# BMS_DAISYCHAIN.net
KiCad netlist of a schematic drawn in Altium Designer
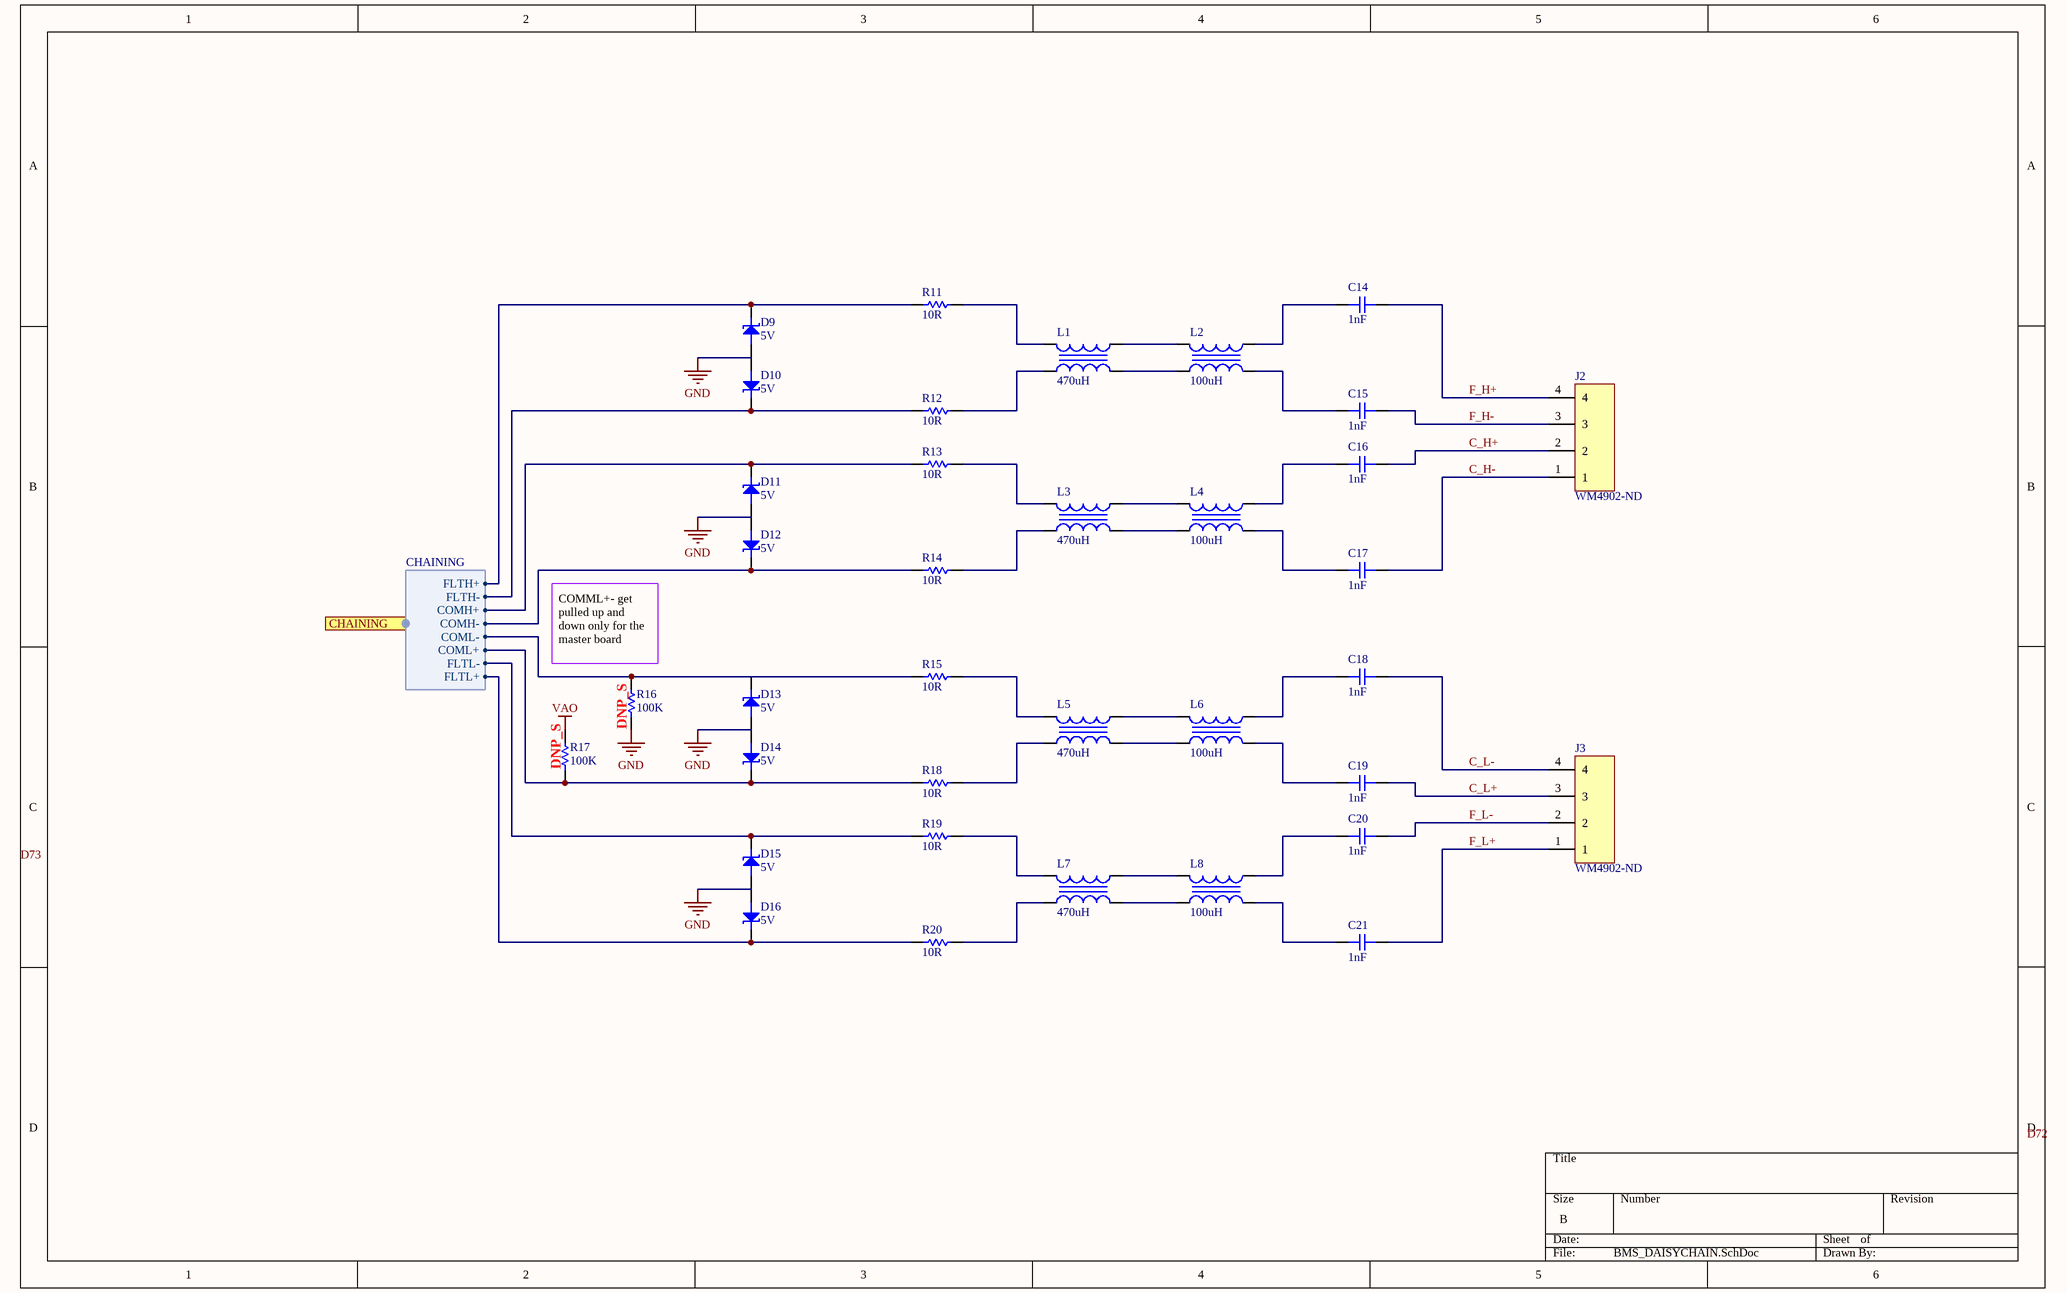
[diagram p0: BMS_DAISYCHAIN.SchDoc]

(export (version "E")
  (design (tool "Eeschema 10.0.6"))
  (components
    (comp (ref "C14")
      (value "1nF")
      (footprint "CAP-0603")
      (description "CAP CER 1000PF 50V X7R 0603")
      (fields
        (field (name "MANUFACTURER") "KEMET")
        (field (name "MANUFACTURER PART NUMBER") "C0603C102J5RACTU")
      )
      (libsource (lib "Capacitors") (part "0603-1nF-50V"))
    )
    (comp (ref "C15")
      (value "1nF")
      (footprint "CAP-0603")
      (description "CAP CER 1000PF 50V X7R 0603")
      (fields
        (field (name "MANUFACTURER") "KEMET")
        (field (name "MANUFACTURER PART NUMBER") "C0603C102J5RACTU")
      )
      (libsource (lib "Capacitors") (part "0603-1nF-50V"))
    )
    (comp (ref "C16")
      (value "1nF")
      (footprint "CAP-0603")
      (description "CAP CER 1000PF 50V X7R 0603")
      (fields
        (field (name "MANUFACTURER") "KEMET")
        (field (name "MANUFACTURER PART NUMBER") "C0603C102J5RACTU")
      )
      (libsource (lib "Capacitors") (part "0603-1nF-50V"))
    )
    (comp (ref "C17")
      (value "1nF")
      (footprint "CAP-0603")
      (description "CAP CER 1000PF 50V X7R 0603")
      (fields
        (field (name "MANUFACTURER") "KEMET")
        (field (name "MANUFACTURER PART NUMBER") "C0603C102J5RACTU")
      )
      (libsource (lib "Capacitors") (part "0603-1nF-50V"))
    )
    (comp (ref "C18")
      (value "1nF")
      (footprint "CAP-0603")
      (description "CAP CER 1000PF 50V X7R 0603")
      (fields
        (field (name "MANUFACTURER") "KEMET")
        (field (name "MANUFACTURER PART NUMBER") "C0603C102J5RACTU")
      )
      (libsource (lib "Capacitors") (part "0603-1nF-50V"))
    )
    (comp (ref "C19")
      (value "1nF")
      (footprint "CAP-0603")
      (description "CAP CER 1000PF 50V X7R 0603")
      (fields
        (field (name "MANUFACTURER") "KEMET")
        (field (name "MANUFACTURER PART NUMBER") "C0603C102J5RACTU")
      )
      (libsource (lib "Capacitors") (part "0603-1nF-50V"))
    )
    (comp (ref "C20")
      (value "1nF")
      (footprint "CAP-0603")
      (description "CAP CER 1000PF 50V X7R 0603")
      (fields
        (field (name "MANUFACTURER") "KEMET")
        (field (name "MANUFACTURER PART NUMBER") "C0603C102J5RACTU")
      )
      (libsource (lib "Capacitors") (part "0603-1nF-50V"))
    )
    (comp (ref "C21")
      (value "1nF")
      (footprint "CAP-0603")
      (description "CAP CER 1000PF 50V X7R 0603")
      (fields
        (field (name "MANUFACTURER") "KEMET")
        (field (name "MANUFACTURER PART NUMBER") "C0603C102J5RACTU")
      )
      (libsource (lib "Capacitors") (part "0603-1nF-50V"))
    )
    (comp (ref "D9")
      (value "5V")
      (footprint "DIODE-SOD323")
      (description "TVS DIODE 5V SOD323")
      (fields
        (field (name "MANUFACTURER") "Nexperia")
        (field (name "MANUFACTURER PART NUMBER") "PESD5V0U1UA,115")
      )
      (libsource (lib "Diodes") (part "TVS-5V"))
    )
    (comp (ref "D10")
      (value "5V")
      (footprint "DIODE-SOD323")
      (description "TVS DIODE 5V SOD323")
      (fields
        (field (name "MANUFACTURER") "Nexperia")
        (field (name "MANUFACTURER PART NUMBER") "PESD5V0U1UA,115")
      )
      (libsource (lib "Diodes") (part "TVS-5V"))
    )
    (comp (ref "D11")
      (value "5V")
      (footprint "DIODE-SOD323")
      (description "TVS DIODE 5V SOD323")
      (fields
        (field (name "MANUFACTURER") "Nexperia")
        (field (name "MANUFACTURER PART NUMBER") "PESD5V0U1UA,115")
      )
      (libsource (lib "Diodes") (part "TVS-5V"))
    )
    (comp (ref "D12")
      (value "5V")
      (footprint "DIODE-SOD323")
      (description "TVS DIODE 5V SOD323")
      (fields
        (field (name "MANUFACTURER") "Nexperia")
        (field (name "MANUFACTURER PART NUMBER") "PESD5V0U1UA,115")
      )
      (libsource (lib "Diodes") (part "TVS-5V"))
    )
    (comp (ref "D13")
      (value "5V")
      (footprint "DIODE-SOD323")
      (description "TVS DIODE 5V SOD323")
      (fields
        (field (name "MANUFACTURER") "Nexperia")
        (field (name "MANUFACTURER PART NUMBER") "PESD5V0U1UA,115")
      )
      (libsource (lib "Diodes") (part "TVS-5V"))
    )
    (comp (ref "D14")
      (value "5V")
      (footprint "DIODE-SOD323")
      (description "TVS DIODE 5V SOD323")
      (fields
        (field (name "MANUFACTURER") "Nexperia")
        (field (name "MANUFACTURER PART NUMBER") "PESD5V0U1UA,115")
      )
      (libsource (lib "Diodes") (part "TVS-5V"))
    )
    (comp (ref "D15")
      (value "5V")
      (footprint "DIODE-SOD323")
      (description "TVS DIODE 5V SOD323")
      (fields
        (field (name "MANUFACTURER") "Nexperia")
        (field (name "MANUFACTURER PART NUMBER") "PESD5V0U1UA,115")
      )
      (libsource (lib "Diodes") (part "TVS-5V"))
    )
    (comp (ref "D16")
      (value "5V")
      (footprint "DIODE-SOD323")
      (description "TVS DIODE 5V SOD323")
      (fields
        (field (name "MANUFACTURER") "Nexperia")
        (field (name "MANUFACTURER PART NUMBER") "PESD5V0U1UA,115")
      )
      (libsource (lib "Diodes") (part "TVS-5V"))
    )
    (comp (ref "J2")
      (value "WM4902-ND")
      (footprint "4PIN")
      (description "CONN HEADER R/A 4POS 2.54MM")
      (fields (field (name "MANUFACTURER") "Molex") (field (name "MANUFACTURER PART NUMBER") "70553-0003"))
      (libsource (lib "Connectors") (part "4PIN"))
    )
    (comp (ref "J3")
      (value "WM4902-ND")
      (footprint "4PIN")
      (description "CONN HEADER R/A 4POS 2.54MM")
      (fields (field (name "MANUFACTURER") "Molex") (field (name "MANUFACTURER PART NUMBER") "70553-0003"))
      (libsource (lib "Connectors") (part "4PIN"))
    )
    (comp (ref "L1")
      (value "470uH")
      (footprint "CMC470u")
      (description "470µH @ 100kHz 2 Line Common Mode Choke SMD 2.2 kOhms")
      (fields
        (field (name "MANUFACTURER") "Wurth Electronics")
        (field (name "MANUFACTURER PART NUMBER") "744242471")
      )
      (libsource (lib "Inductors") (part "CMC-470uH"))
    )
    (comp (ref "L2")
      (value "100uH")
      (footprint "CMC100U")
      (description "100µH @ 100kHz 2 Line Common Mode Choke SMD 5.8 kOhms")
      (fields
        (field (name "MANUFACTURER") "TDK EPCOS")
        (field (name "MANUFACTURER PART NUMBER") "B82787C0104H002")
      )
      (libsource (lib "Inductors") (part "CMC-100uH"))
    )
    (comp (ref "L3")
      (value "470uH")
      (footprint "CMC470u")
      (description "470µH @ 100kHz 2 Line Common Mode Choke SMD 2.2 kOhms")
      (fields
        (field (name "MANUFACTURER") "Wurth Electronics")
        (field (name "MANUFACTURER PART NUMBER") "744242471")
      )
      (libsource (lib "Inductors") (part "CMC-470uH"))
    )
    (comp (ref "L4")
      (value "100uH")
      (footprint "CMC100U")
      (description "100µH @ 100kHz 2 Line Common Mode Choke SMD 5.8 kOhms")
      (fields
        (field (name "MANUFACTURER") "TDK EPCOS")
        (field (name "MANUFACTURER PART NUMBER") "B82787C0104H002")
      )
      (libsource (lib "Inductors") (part "CMC-100uH"))
    )
    (comp (ref "L5")
      (value "470uH")
      (footprint "CMC470u")
      (description "470µH @ 100kHz 2 Line Common Mode Choke SMD 2.2 kOhms")
      (fields
        (field (name "MANUFACTURER") "Wurth Electronics")
        (field (name "MANUFACTURER PART NUMBER") "744242471")
      )
      (libsource (lib "Inductors") (part "CMC-470uH"))
    )
    (comp (ref "L6")
      (value "100uH")
      (footprint "CMC100U")
      (description "100µH @ 100kHz 2 Line Common Mode Choke SMD 5.8 kOhms")
      (fields
        (field (name "MANUFACTURER") "TDK EPCOS")
        (field (name "MANUFACTURER PART NUMBER") "B82787C0104H002")
      )
      (libsource (lib "Inductors") (part "CMC-100uH"))
    )
    (comp (ref "L7")
      (value "470uH")
      (footprint "CMC470u")
      (description "470µH @ 100kHz 2 Line Common Mode Choke SMD 2.2 kOhms")
      (fields
        (field (name "MANUFACTURER") "Wurth Electronics")
        (field (name "MANUFACTURER PART NUMBER") "744242471")
      )
      (libsource (lib "Inductors") (part "CMC-470uH"))
    )
    (comp (ref "L8")
      (value "100uH")
      (footprint "CMC100U")
      (description "100µH @ 100kHz 2 Line Common Mode Choke SMD 5.8 kOhms")
      (fields
        (field (name "MANUFACTURER") "TDK EPCOS")
        (field (name "MANUFACTURER PART NUMBER") "B82787C0104H002")
      )
      (libsource (lib "Inductors") (part "CMC-100uH"))
    )
    (comp (ref "R11")
      (value "10R")
      (footprint "RES-0603")
      (description "RES SMD 10 OHM 1% 1/10W 0603")
      (fields
        (field (name "MANUFACTURER") "Yageo")
        (field (name "MANUFACTURER PART NUMBER") "RC0603FR-0710RL")
      )
      (libsource (lib "Resistors") (part "0603-10R"))
    )
    (comp (ref "R12")
      (value "10R")
      (footprint "RES-0603")
      (description "RES SMD 10 OHM 1% 1/10W 0603")
      (fields
        (field (name "MANUFACTURER") "Yageo")
        (field (name "MANUFACTURER PART NUMBER") "RC0603FR-0710RL")
      )
      (libsource (lib "Resistors") (part "0603-10R"))
    )
    (comp (ref "R13")
      (value "10R")
      (footprint "RES-0603")
      (description "RES SMD 10 OHM 1% 1/10W 0603")
      (fields
        (field (name "MANUFACTURER") "Yageo")
        (field (name "MANUFACTURER PART NUMBER") "RC0603FR-0710RL")
      )
      (libsource (lib "Resistors") (part "0603-10R"))
    )
    (comp (ref "R14")
      (value "10R")
      (footprint "RES-0603")
      (description "RES SMD 10 OHM 1% 1/10W 0603")
      (fields
        (field (name "MANUFACTURER") "Yageo")
        (field (name "MANUFACTURER PART NUMBER") "RC0603FR-0710RL")
      )
      (libsource (lib "Resistors") (part "0603-10R"))
    )
    (comp (ref "R15")
      (value "10R")
      (footprint "RES-0603")
      (description "RES SMD 10 OHM 1% 1/10W 0603")
      (fields
        (field (name "MANUFACTURER") "Yageo")
        (field (name "MANUFACTURER PART NUMBER") "RC0603FR-0710RL")
      )
      (libsource (lib "Resistors") (part "0603-10R"))
    )
    (comp (ref "R16")
      (value "100K")
      (footprint "RES-0603")
      (description "RES 100K OHM 1% 1/10W 0603")
      (fields
        (field (name "MANUFACTURER") "Stackpole Electronics")
        (field (name "MANUFACTURER PART NUMBER") "RMCF0603FT100K")
      )
      (libsource (lib "Resistors") (part "0603-100KR"))
    )
    (comp (ref "R17")
      (value "100K")
      (footprint "RES-0603")
      (description "RES 100K OHM 1% 1/10W 0603")
      (fields
        (field (name "MANUFACTURER") "Stackpole Electronics")
        (field (name "MANUFACTURER PART NUMBER") "RMCF0603FT100K")
      )
      (libsource (lib "Resistors") (part "0603-100KR"))
    )
    (comp (ref "R18")
      (value "10R")
      (footprint "RES-0603")
      (description "RES SMD 10 OHM 1% 1/10W 0603")
      (fields
        (field (name "MANUFACTURER") "Yageo")
        (field (name "MANUFACTURER PART NUMBER") "RC0603FR-0710RL")
      )
      (libsource (lib "Resistors") (part "0603-10R"))
    )
    (comp (ref "R19")
      (value "10R")
      (footprint "RES-0603")
      (description "RES SMD 10 OHM 1% 1/10W 0603")
      (fields
        (field (name "MANUFACTURER") "Yageo")
        (field (name "MANUFACTURER PART NUMBER") "RC0603FR-0710RL")
      )
      (libsource (lib "Resistors") (part "0603-10R"))
    )
    (comp (ref "R20")
      (value "10R")
      (footprint "RES-0603")
      (description "RES SMD 10 OHM 1% 1/10W 0603")
      (fields
        (field (name "MANUFACTURER") "Yageo")
        (field (name "MANUFACTURER PART NUMBER") "RC0603FR-0710RL")
      )
      (libsource (lib "Resistors") (part "0603-10R"))
    )
  )
  (nets
    (net (code "2") (name "/C_H+") (class "Default")
      (node (ref "C16") (pin "2") (pinfunction "2_2") (pintype "passive"))
      (node (ref "J2") (pin "2") (pinfunction "2_2") (pintype "passive"))
    )
    (net (code "3") (name "/C_H-") (class "Default")
      (node (ref "C17") (pin "2") (pinfunction "2_2") (pintype "passive"))
      (node (ref "J2") (pin "1") (pinfunction "1_1") (pintype "passive"))
    )
    (net (code "4") (name "/C_L+") (class "Default")
      (node (ref "C19") (pin "2") (pinfunction "2_2") (pintype "passive"))
      (node (ref "J3") (pin "3") (pinfunction "3_3") (pintype "passive"))
    )
    (net (code "5") (name "/C_L-") (class "Default")
      (node (ref "C18") (pin "2") (pinfunction "2_2") (pintype "passive"))
      (node (ref "J3") (pin "4") (pinfunction "4_4") (pintype "passive"))
    )
    (net (code "8") (name "/F_H+") (class "Default")
      (node (ref "C14") (pin "2") (pinfunction "2_2") (pintype "passive"))
      (node (ref "J2") (pin "4") (pinfunction "4_4") (pintype "passive"))
    )
    (net (code "9") (name "/F_H-") (class "Default")
      (node (ref "C15") (pin "2") (pinfunction "2_2") (pintype "passive"))
      (node (ref "J2") (pin "3") (pinfunction "3_3") (pintype "passive"))
    )
    (net (code "10") (name "/F_L+") (class "Default")
      (node (ref "C21") (pin "2") (pinfunction "2_2") (pintype "passive"))
      (node (ref "J3") (pin "1") (pinfunction "1_1") (pintype "passive"))
    )
    (net (code "11") (name "/F_L-") (class "Default")
      (node (ref "C20") (pin "2") (pinfunction "2_2") (pintype "passive"))
      (node (ref "J3") (pin "2") (pinfunction "2_2") (pintype "passive"))
    )
    (net (code "13") (name "GND") (class "Default")
      (node (ref "D10") (pin "2") (pinfunction "2_2") (pintype "passive"))
      (node (ref "D11") (pin "2") (pinfunction "2_2") (pintype "passive"))
      (node (ref "D12") (pin "2") (pinfunction "2_2") (pintype "passive"))
      (node (ref "D13") (pin "2") (pinfunction "2_2") (pintype "passive"))
      (node (ref "D14") (pin "2") (pinfunction "2_2") (pintype "passive"))
      (node (ref "D15") (pin "2") (pinfunction "2_2") (pintype "passive"))
      (node (ref "D16") (pin "2") (pinfunction "2_2") (pintype "passive"))
      (node (ref "D9") (pin "2") (pinfunction "2_2") (pintype "passive"))
      (node (ref "R16") (pin "1") (pinfunction "1_1") (pintype "passive"))
    )
    (net (code "14") (name "Net-(C14-Pad1)") (class "Default")
      (node (ref "C14") (pin "1") (pinfunction "1_1") (pintype "passive"))
      (node (ref "L2") (pin "4") (pinfunction "4_4") (pintype "passive"))
    )
    (net (code "15") (name "Net-(C15-Pad1)") (class "Default")
      (node (ref "C15") (pin "1") (pinfunction "1_1") (pintype "passive"))
      (node (ref "L2") (pin "3") (pinfunction "3_3") (pintype "passive"))
    )
    (net (code "16") (name "Net-(C16-Pad1)") (class "Default")
      (node (ref "C16") (pin "1") (pinfunction "1_1") (pintype "passive"))
      (node (ref "L4") (pin "4") (pinfunction "4_4") (pintype "passive"))
    )
    (net (code "17") (name "Net-(C17-Pad1)") (class "Default")
      (node (ref "C17") (pin "1") (pinfunction "1_1") (pintype "passive"))
      (node (ref "L4") (pin "3") (pinfunction "3_3") (pintype "passive"))
    )
    (net (code "18") (name "Net-(C18-Pad1)") (class "Default")
      (node (ref "C18") (pin "1") (pinfunction "1_1") (pintype "passive"))
      (node (ref "L6") (pin "4") (pinfunction "4_4") (pintype "passive"))
    )
    (net (code "19") (name "Net-(C19-Pad1)") (class "Default")
      (node (ref "C19") (pin "1") (pinfunction "1_1") (pintype "passive"))
      (node (ref "L6") (pin "3") (pinfunction "3_3") (pintype "passive"))
    )
    (net (code "20") (name "Net-(C20-Pad1)") (class "Default")
      (node (ref "C20") (pin "1") (pinfunction "1_1") (pintype "passive"))
      (node (ref "L8") (pin "4") (pinfunction "4_4") (pintype "passive"))
    )
    (net (code "21") (name "Net-(C21-Pad1)") (class "Default")
      (node (ref "C21") (pin "1") (pinfunction "1_1") (pintype "passive"))
      (node (ref "L8") (pin "3") (pinfunction "3_3") (pintype "passive"))
    )
    (net (code "22") (name "Net-(D9-Pad1)") (class "Default")
      (node (ref "D9") (pin "1") (pinfunction "1_1") (pintype "passive"))
      (node (ref "R11") (pin "1") (pinfunction "1_1") (pintype "passive"))
    )
    (net (code "23") (name "Net-(D10-Pad1)") (class "Default")
      (node (ref "D10") (pin "1") (pinfunction "1_1") (pintype "passive"))
      (node (ref "R12") (pin "1") (pinfunction "1_1") (pintype "passive"))
    )
    (net (code "24") (name "Net-(D11-Pad1)") (class "Default")
      (node (ref "D11") (pin "1") (pinfunction "1_1") (pintype "passive"))
      (node (ref "R13") (pin "1") (pinfunction "1_1") (pintype "passive"))
    )
    (net (code "25") (name "Net-(D12-Pad1)") (class "Default")
      (node (ref "D12") (pin "1") (pinfunction "1_1") (pintype "passive"))
      (node (ref "R14") (pin "1") (pinfunction "1_1") (pintype "passive"))
    )
    (net (code "26") (name "Net-(D13-Pad1)") (class "Default")
      (node (ref "D13") (pin "1") (pinfunction "1_1") (pintype "passive"))
      (node (ref "R15") (pin "1") (pinfunction "1_1") (pintype "passive"))
      (node (ref "R16") (pin "2") (pinfunction "2_2") (pintype "passive"))
    )
    (net (code "27") (name "Net-(D14-Pad1)") (class "Default")
      (node (ref "D14") (pin "1") (pinfunction "1_1") (pintype "passive"))
      (node (ref "R17") (pin "1") (pinfunction "1_1") (pintype "passive"))
      (node (ref "R18") (pin "1") (pinfunction "1_1") (pintype "passive"))
    )
    (net (code "28") (name "Net-(D15-Pad1)") (class "Default")
      (node (ref "D15") (pin "1") (pinfunction "1_1") (pintype "passive"))
      (node (ref "R19") (pin "1") (pinfunction "1_1") (pintype "passive"))
    )
    (net (code "29") (name "Net-(D16-Pad1)") (class "Default")
      (node (ref "D16") (pin "1") (pinfunction "1_1") (pintype "passive"))
      (node (ref "R20") (pin "1") (pinfunction "1_1") (pintype "passive"))
    )
    (net (code "30") (name "Net-(L1-Pad1)") (class "Default")
      (node (ref "L1") (pin "1") (pinfunction "1_1") (pintype "passive"))
      (node (ref "R11") (pin "2") (pinfunction "2_2") (pintype "passive"))
    )
    (net (code "31") (name "Net-(L1-Pad2)") (class "Default")
      (node (ref "L1") (pin "2") (pinfunction "2_2") (pintype "passive"))
      (node (ref "R12") (pin "2") (pinfunction "2_2") (pintype "passive"))
    )
    (net (code "32") (name "Net-(L1-Pad3)") (class "Default")
      (node (ref "L1") (pin "3") (pinfunction "3_3") (pintype "passive"))
      (node (ref "L2") (pin "2") (pinfunction "2_2") (pintype "passive"))
    )
    (net (code "33") (name "Net-(L1-Pad4)") (class "Default")
      (node (ref "L1") (pin "4") (pinfunction "4_4") (pintype "passive"))
      (node (ref "L2") (pin "1") (pinfunction "1_1") (pintype "passive"))
    )
    (net (code "34") (name "Net-(L3-Pad1)") (class "Default")
      (node (ref "L3") (pin "1") (pinfunction "1_1") (pintype "passive"))
      (node (ref "R13") (pin "2") (pinfunction "2_2") (pintype "passive"))
    )
    (net (code "35") (name "Net-(L3-Pad2)") (class "Default")
      (node (ref "L3") (pin "2") (pinfunction "2_2") (pintype "passive"))
      (node (ref "R14") (pin "2") (pinfunction "2_2") (pintype "passive"))
    )
    (net (code "36") (name "Net-(L3-Pad3)") (class "Default")
      (node (ref "L3") (pin "3") (pinfunction "3_3") (pintype "passive"))
      (node (ref "L4") (pin "2") (pinfunction "2_2") (pintype "passive"))
    )
    (net (code "37") (name "Net-(L3-Pad4)") (class "Default")
      (node (ref "L3") (pin "4") (pinfunction "4_4") (pintype "passive"))
      (node (ref "L4") (pin "1") (pinfunction "1_1") (pintype "passive"))
    )
    (net (code "38") (name "Net-(L5-Pad1)") (class "Default")
      (node (ref "L5") (pin "1") (pinfunction "1_1") (pintype "passive"))
      (node (ref "R15") (pin "2") (pinfunction "2_2") (pintype "passive"))
    )
    (net (code "39") (name "Net-(L5-Pad2)") (class "Default")
      (node (ref "L5") (pin "2") (pinfunction "2_2") (pintype "passive"))
      (node (ref "R18") (pin "2") (pinfunction "2_2") (pintype "passive"))
    )
    (net (code "40") (name "Net-(L5-Pad3)") (class "Default")
      (node (ref "L5") (pin "3") (pinfunction "3_3") (pintype "passive"))
      (node (ref "L6") (pin "2") (pinfunction "2_2") (pintype "passive"))
    )
    (net (code "41") (name "Net-(L5-Pad4)") (class "Default")
      (node (ref "L5") (pin "4") (pinfunction "4_4") (pintype "passive"))
      (node (ref "L6") (pin "1") (pinfunction "1_1") (pintype "passive"))
    )
    (net (code "42") (name "Net-(L7-Pad1)") (class "Default")
      (node (ref "L7") (pin "1") (pinfunction "1_1") (pintype "passive"))
      (node (ref "R19") (pin "2") (pinfunction "2_2") (pintype "passive"))
    )
    (net (code "43") (name "Net-(L7-Pad2)") (class "Default")
      (node (ref "L7") (pin "2") (pinfunction "2_2") (pintype "passive"))
      (node (ref "R20") (pin "2") (pinfunction "2_2") (pintype "passive"))
    )
    (net (code "44") (name "Net-(L7-Pad3)") (class "Default")
      (node (ref "L7") (pin "3") (pinfunction "3_3") (pintype "passive"))
      (node (ref "L8") (pin "2") (pinfunction "2_2") (pintype "passive"))
    )
    (net (code "45") (name "Net-(L7-Pad4)") (class "Default")
      (node (ref "L7") (pin "4") (pinfunction "4_4") (pintype "passive"))
      (node (ref "L8") (pin "1") (pinfunction "1_1") (pintype "passive"))
    )
    (net (code "46") (name "VAO") (class "Default")
      (node (ref "R17") (pin "2") (pinfunction "2_2") (pintype "passive"))
    )
  )
)
